# ProPrj___2026-05-07.net
KiCad netlist of a schematic drawn in EasyEDA Pro
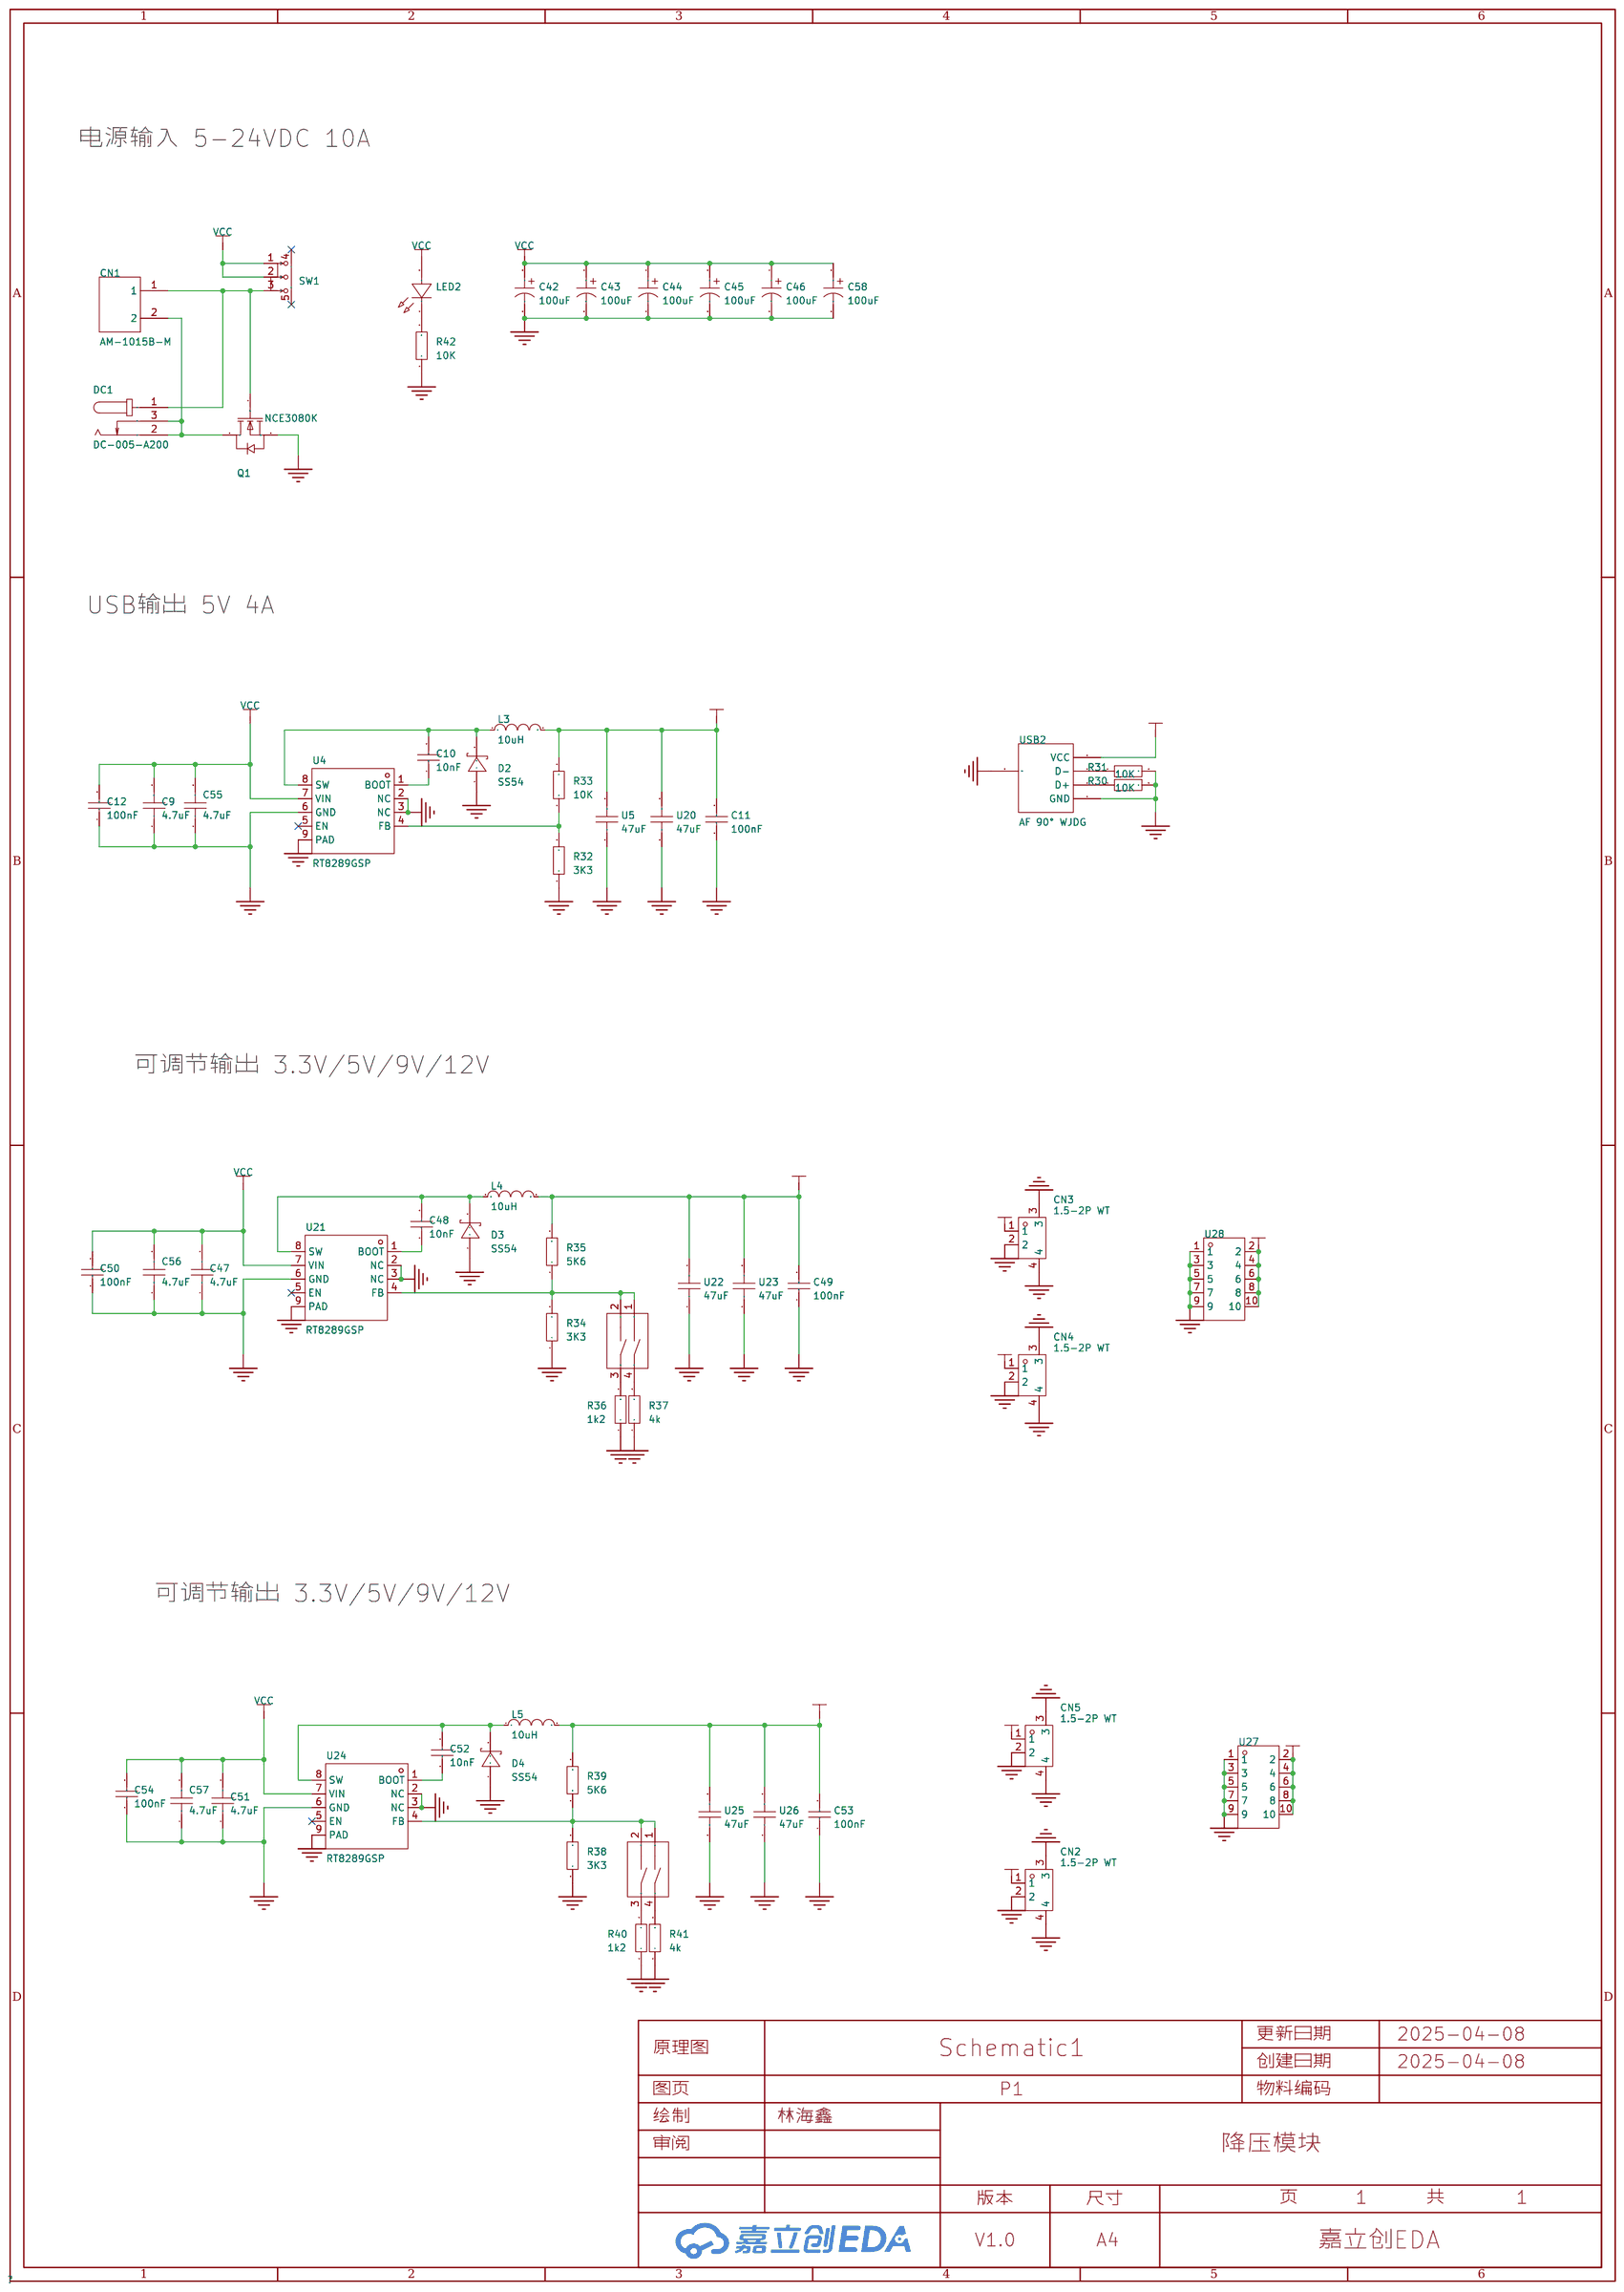
[diagram p0: schematic sheet]

(export (version "E")
  (design (tool "Eeschema 10.0.6"))
  (components
    (comp (ref "C9")
      (value "4.7uF")
      (fields
        (field (name "Manufacturer Part") "CL31B475KBHNNNE")
        (field (name "Manufacturer") "SAMSUNG(三星)")
      )
      (libsource (lib "easyedapro") (part "tcc0603x5r475k250ct"))
    )
    (comp (ref "C10")
      (value "10nF")
      (footprint "easyedapro:C0402")
      (description "容值:100nF;精度:±10%;额定电压:16V;材质(温度系数):X7R;")
      (fields
        (field (name "Manufacturer Part") "CC0603KRX7R9BB103")
        (field (name "Manufacturer") "YAGEO(国巨)")
      )
      (libsource (lib "easyedapro") (part "CL05B104KO5NNNC"))
    )
    (comp (ref "C11")
      (value "100nF")
      (footprint "easyedapro:C0402")
      (description "容值:100nF;精度:±10%;额定电压:16V;材质(温度系数):X7R;")
      (fields
        (field (name "Manufacturer Part") "CGA0603X7R104K500JT")
        (field (name "Manufacturer") "HRE(芯声)")
      )
      (libsource (lib "easyedapro") (part "CL05B104KO5NNNC"))
    )
    (comp (ref "C12")
      (value "100nF")
      (footprint "easyedapro:C0402")
      (description "容值:100nF;精度:±10%;额定电压:16V;材质(温度系数):X7R;")
      (fields
        (field (name "Manufacturer Part") "CGA0603X7R104K500JT")
        (field (name "Manufacturer") "HRE(芯声)")
      )
      (libsource (lib "easyedapro") (part "CL05B104KO5NNNC"))
    )
    (comp (ref "C42")
      (value "100uF")
      (footprint "easyedapro:CAP-SMD_BD6.3-L6.6-W6.6-LS7.6-FD-1")
      (description "容值:100uF;精度:±20%;额定电压:35V;纹波电流:230mA@120Hz;等效串联电阻:600mΩ@100kHz;")
      (fields
        (field (name "Manufacturer Part") "RVE100UF35V67RV0072")
        (field (name "Manufacturer") "KNSCHA(科尼盛)")
      )
      (libsource (lib "easyedapro") (part "rve100uf35v67rv0072"))
    )
    (comp (ref "C43")
      (value "100uF")
      (footprint "easyedapro:CAP-SMD_BD6.3-L6.6-W6.6-LS7.6-FD-1")
      (description "容值:100uF;精度:±20%;额定电压:35V;纹波电流:230mA@120Hz;等效串联电阻:600mΩ@100kHz;")
      (fields
        (field (name "Manufacturer Part") "RVE100UF35V67RV0072")
        (field (name "Manufacturer") "KNSCHA(科尼盛)")
      )
      (libsource (lib "easyedapro") (part "rve100uf35v67rv0072"))
    )
    (comp (ref "C44")
      (value "100uF")
      (footprint "easyedapro:CAP-SMD_BD6.3-L6.6-W6.6-LS7.6-FD-1")
      (description "容值:100uF;精度:±20%;额定电压:35V;纹波电流:230mA@120Hz;等效串联电阻:600mΩ@100kHz;")
      (fields
        (field (name "Manufacturer Part") "RVE100UF35V67RV0072")
        (field (name "Manufacturer") "KNSCHA(科尼盛)")
      )
      (libsource (lib "easyedapro") (part "rve100uf35v67rv0072"))
    )
    (comp (ref "C45")
      (value "100uF")
      (footprint "easyedapro:CAP-SMD_BD6.3-L6.6-W6.6-LS7.6-FD-1")
      (description "容值:100uF;精度:±20%;额定电压:35V;纹波电流:230mA@120Hz;等效串联电阻:600mΩ@100kHz;")
      (fields
        (field (name "Manufacturer Part") "RVE100UF35V67RV0072")
        (field (name "Manufacturer") "KNSCHA(科尼盛)")
      )
      (libsource (lib "easyedapro") (part "rve100uf35v67rv0072"))
    )
    (comp (ref "C46")
      (value "100uF")
      (footprint "easyedapro:CAP-SMD_BD6.3-L6.6-W6.6-LS7.6-FD-1")
      (description "容值:100uF;精度:±20%;额定电压:35V;纹波电流:230mA@120Hz;等效串联电阻:600mΩ@100kHz;")
      (fields
        (field (name "Manufacturer Part") "RVE100UF35V67RV0072")
        (field (name "Manufacturer") "KNSCHA(科尼盛)")
      )
      (libsource (lib "easyedapro") (part "rve100uf35v67rv0072"))
    )
    (comp (ref "C47")
      (value "4.7uF")
      (fields
        (field (name "Manufacturer Part") "CL31B475KBHNNNE")
        (field (name "Manufacturer") "SAMSUNG(三星)")
      )
      (libsource (lib "easyedapro") (part "tcc0603x5r475k250ct"))
    )
    (comp (ref "C48")
      (value "10nF")
      (footprint "easyedapro:C0402")
      (description "容值:100nF;精度:±10%;额定电压:16V;材质(温度系数):X7R;")
      (fields
        (field (name "Manufacturer Part") "CC0603KRX7R9BB103")
        (field (name "Manufacturer") "YAGEO(国巨)")
      )
      (libsource (lib "easyedapro") (part "CL05B104KO5NNNC"))
    )
    (comp (ref "C49")
      (value "100nF")
      (footprint "easyedapro:C0402")
      (description "容值:100nF;精度:±10%;额定电压:16V;材质(温度系数):X7R;")
      (fields
        (field (name "Manufacturer Part") "CGA0603X7R104K500JT")
        (field (name "Manufacturer") "HRE(芯声)")
      )
      (libsource (lib "easyedapro") (part "CL05B104KO5NNNC"))
    )
    (comp (ref "C50")
      (value "100nF")
      (footprint "easyedapro:C0402")
      (description "容值:100nF;精度:±10%;额定电压:16V;材质(温度系数):X7R;")
      (fields
        (field (name "Manufacturer Part") "CGA0603X7R104K500JT")
        (field (name "Manufacturer") "HRE(芯声)")
      )
      (libsource (lib "easyedapro") (part "CL05B104KO5NNNC"))
    )
    (comp (ref "C51")
      (value "4.7uF")
      (fields
        (field (name "Manufacturer Part") "CL31B475KBHNNNE")
        (field (name "Manufacturer") "SAMSUNG(三星)")
      )
      (libsource (lib "easyedapro") (part "tcc0603x5r475k250ct"))
    )
    (comp (ref "C52")
      (value "10nF")
      (footprint "easyedapro:C0402")
      (description "容值:100nF;精度:±10%;额定电压:16V;材质(温度系数):X7R;")
      (fields
        (field (name "Manufacturer Part") "CC0603KRX7R9BB103")
        (field (name "Manufacturer") "YAGEO(国巨)")
      )
      (libsource (lib "easyedapro") (part "CL05B104KO5NNNC"))
    )
    (comp (ref "C53")
      (value "100nF")
      (footprint "easyedapro:C0402")
      (description "容值:100nF;精度:±10%;额定电压:16V;材质(温度系数):X7R;")
      (fields
        (field (name "Manufacturer Part") "CGA0603X7R104K500JT")
        (field (name "Manufacturer") "HRE(芯声)")
      )
      (libsource (lib "easyedapro") (part "CL05B104KO5NNNC"))
    )
    (comp (ref "C54")
      (value "100nF")
      (footprint "easyedapro:C0402")
      (description "容值:100nF;精度:±10%;额定电压:16V;材质(温度系数):X7R;")
      (fields
        (field (name "Manufacturer Part") "CGA0603X7R104K500JT")
        (field (name "Manufacturer") "HRE(芯声)")
      )
      (libsource (lib "easyedapro") (part "CL05B104KO5NNNC"))
    )
    (comp (ref "C55")
      (value "4.7uF")
      (fields
        (field (name "Manufacturer Part") "CL31B475KBHNNNE")
        (field (name "Manufacturer") "SAMSUNG(三星)")
      )
      (libsource (lib "easyedapro") (part "tcc0603x5r475k250ct"))
    )
    (comp (ref "C56")
      (value "4.7uF")
      (fields
        (field (name "Manufacturer Part") "CL31B475KBHNNNE")
        (field (name "Manufacturer") "SAMSUNG(三星)")
      )
      (libsource (lib "easyedapro") (part "tcc0603x5r475k250ct"))
    )
    (comp (ref "C57")
      (value "4.7uF")
      (fields
        (field (name "Manufacturer Part") "CL31B475KBHNNNE")
        (field (name "Manufacturer") "SAMSUNG(三星)")
      )
      (libsource (lib "easyedapro") (part "tcc0603x5r475k250ct"))
    )
    (comp (ref "C58")
      (value "100uF")
      (footprint "easyedapro:CAP-SMD_BD6.3-L6.6-W6.6-LS7.6-FD-1")
      (description "容值:100uF;精度:±20%;额定电压:35V;纹波电流:230mA@120Hz;等效串联电阻:600mΩ@100kHz;")
      (fields
        (field (name "Manufacturer Part") "RVE100UF35V67RV0072")
        (field (name "Manufacturer") "KNSCHA(科尼盛)")
      )
      (libsource (lib "easyedapro") (part "rve100uf35v67rv0072"))
    )
    (comp (ref "CN1")
      (value "AM-1015B-M")
      (footprint "easyedapro:CONN-TH_AM-1015B-M")
      (description "类别:-;类型1:-;")
      (fields (field (name "Manufacturer") "AMASS(艾迈斯)"))
      (libsource (lib "easyedapro") (part "AM-1015B-M"))
    )
    (comp (ref "CN2")
      (value "1.5-2P WT")
      (footprint "easyedapro:CONN-SMD_1.5-2P-WT")
      (description "插针结构:1x2P;间距:1.5mm;安装方式:卧贴;参考系列:ZH;总PIN数:2P;排数:1;每排PIN数:2;行距:-;额定电流:1A;工作温度范围:-25°C~+85°C;")
      (fields (field (name "Manufacturer") "SHOU HAN(首韩)"))
      (libsource (lib "easyedapro") (part "1.5-2P WT"))
    )
    (comp (ref "CN3")
      (value "1.5-2P WT")
      (footprint "easyedapro:CONN-SMD_1.5-2P-WT")
      (description "插针结构:1x2P;间距:1.5mm;安装方式:卧贴;参考系列:ZH;总PIN数:2P;排数:1;每排PIN数:2;行距:-;额定电流:1A;工作温度范围:-25°C~+85°C;")
      (fields (field (name "Manufacturer") "SHOU HAN(首韩)"))
      (libsource (lib "easyedapro") (part "1.5-2P WT"))
    )
    (comp (ref "CN4")
      (value "1.5-2P WT")
      (footprint "easyedapro:CONN-SMD_1.5-2P-WT")
      (description "插针结构:1x2P;间距:1.5mm;安装方式:卧贴;参考系列:ZH;总PIN数:2P;排数:1;每排PIN数:2;行距:-;额定电流:1A;工作温度范围:-25°C~+85°C;")
      (fields (field (name "Manufacturer") "SHOU HAN(首韩)"))
      (libsource (lib "easyedapro") (part "1.5-2P WT"))
    )
    (comp (ref "CN5")
      (value "1.5-2P WT")
      (footprint "easyedapro:CONN-SMD_1.5-2P-WT")
      (description "插针结构:1x2P;间距:1.5mm;安装方式:卧贴;参考系列:ZH;总PIN数:2P;排数:1;每排PIN数:2;行距:-;额定电流:1A;工作温度范围:-25°C~+85°C;")
      (fields (field (name "Manufacturer") "SHOU HAN(首韩)"))
      (libsource (lib "easyedapro") (part "1.5-2P WT"))
    )
    (comp (ref "D2")
      (value "SS54")
      (footprint "easyedapro:SMA_L4.4-W2.8-LS5.4-R-RD")
      (description "正向压降(Vf):550mV@5A;直流反向耐压(Vr):40V;平均整流电流(Io):5A;")
      (fields (field (name "Manufacturer") "MDD"))
      (libsource (lib "easyedapro") (part "SS54_C22452"))
    )
    (comp (ref "D3")
      (value "SS54")
      (footprint "easyedapro:SMA_L4.4-W2.8-LS5.4-R-RD")
      (description "正向压降(Vf):550mV@5A;直流反向耐压(Vr):40V;平均整流电流(Io):5A;")
      (fields (field (name "Manufacturer") "MDD"))
      (libsource (lib "easyedapro") (part "SS54_C22452"))
    )
    (comp (ref "D4")
      (value "SS54")
      (footprint "easyedapro:SMA_L4.4-W2.8-LS5.4-R-RD")
      (description "正向压降(Vf):550mV@5A;直流反向耐压(Vr):40V;平均整流电流(Io):5A;")
      (fields (field (name "Manufacturer") "MDD"))
      (libsource (lib "easyedapro") (part "SS54_C22452"))
    )
    (comp (ref "DC1")
      (value "DC-005-A200")
      (footprint "easyedapro:DC-IN-TH_DC-005-A200")
      (description "连接器类型:DC电源插座;安装方式:弯插;触点内径:2mm;触点外径:6.4mm;额定电流:3A;额定电压:30V;工作温度范围:-20°C~+70°C;")
      (fields (field (name "Manufacturer") "XUNPU(讯普)"))
      (libsource (lib "easyedapro") (part "DC-005-A200"))
    )
    (comp (ref "L3")
      (value "10uH")
      (footprint "easyedapro:IND-SMD_L7.3-W6.8")
      (description "电感值:10uH;精度:±20%;额定电流:4.5A;饱和电流(Isat):5.5A;类型:一体成型电感;")
      (fields (field (name "Manufacturer Part") "FXL0630-100-M") (field (name "Manufacturer") "cjiang(长江微电)"))
      (libsource (lib "easyedapro") (part "FXL0630-100-M"))
    )
    (comp (ref "L4")
      (value "10uH")
      (footprint "easyedapro:IND-SMD_L7.3-W6.8")
      (description "电感值:10uH;精度:±20%;额定电流:4.5A;饱和电流(Isat):5.5A;类型:一体成型电感;")
      (fields (field (name "Manufacturer Part") "FXL0630-100-M") (field (name "Manufacturer") "cjiang(长江微电)"))
      (libsource (lib "easyedapro") (part "FXL0630-100-M"))
    )
    (comp (ref "L5")
      (value "10uH")
      (footprint "easyedapro:IND-SMD_L7.3-W6.8")
      (description "电感值:10uH;精度:±20%;额定电流:4.5A;饱和电流(Isat):5.5A;类型:一体成型电感;")
      (fields (field (name "Manufacturer Part") "FXL0630-100-M") (field (name "Manufacturer") "cjiang(长江微电)"))
      (libsource (lib "easyedapro") (part "FXL0630-100-M"))
    )
    (comp (ref "LED2")
      (value "XL-1608SURC-06")
      (footprint "easyedapro:LED0603-RD_RED")
      (description "发光颜色:红色;功率:55mW;正向电流:25mA;主波长:617nm~621nm;透镜颜色:无色透明透镜;色温:-;发光角度:120°;载带方式:正贴;工作温度:-30°C~+85°C;")
      (fields (field (name "Manufacturer") "XINGLIGHT(成兴光)"))
      (libsource (lib "easyedapro") (part "XL-1608SURC-06"))
    )
    (comp (ref "Q1")
      (value "NCE3080K")
      (footprint "easyedapro:TO-252-2_L6.6-W6.1-P4.57-LS9.9-TL-CW")
      (fields (field (name "Manufacturer") "NCE(无锡新洁能)"))
      (libsource (lib "easyedapro") (part "NCE3080K"))
    )
    (comp (ref "R30") (value "10K") (footprint "easyedapro:R0603") (libsource (lib "easyedapro") (part "电阻")))
    (comp (ref "R31") (value "10K") (footprint "easyedapro:R0603") (libsource (lib "easyedapro") (part "电阻")))
    (comp (ref "R32") (value "3K3") (footprint "easyedapro:R0603") (libsource (lib "easyedapro") (part "电阻")))
    (comp (ref "R33") (value "10K") (footprint "easyedapro:R0603") (libsource (lib "easyedapro") (part "电阻")))
    (comp (ref "R34") (value "3K3") (footprint "easyedapro:R0603") (libsource (lib "easyedapro") (part "电阻")))
    (comp (ref "R35") (value "5K6") (footprint "easyedapro:R0603") (libsource (lib "easyedapro") (part "电阻")))
    (comp (ref "R36") (value "1k2") (footprint "easyedapro:R0603") (libsource (lib "easyedapro") (part "电阻")))
    (comp (ref "R37") (value "4k") (footprint "easyedapro:R0603") (libsource (lib "easyedapro") (part "电阻")))
    (comp (ref "R38") (value "3K3") (footprint "easyedapro:R0603") (libsource (lib "easyedapro") (part "电阻")))
    (comp (ref "R39") (value "5K6") (footprint "easyedapro:R0603") (libsource (lib "easyedapro") (part "电阻")))
    (comp (ref "R40") (value "1k2") (footprint "easyedapro:R0603") (libsource (lib "easyedapro") (part "电阻")))
    (comp (ref "R41") (value "4k") (footprint "easyedapro:R0603") (libsource (lib "easyedapro") (part "电阻")))
    (comp (ref "R42") (value "10K") (footprint "easyedapro:R0603") (libsource (lib "easyedapro") (part "电阻")))
    (comp (ref "SW1")
      (value "SS-12D11L5")
      (footprint "easyedapro:SW-TH_SS-12D11L5")
      (description "电路结构:单刀双掷;安装方式:侧插;开关颜色:黑色;额定电流(DC):3A;额定电压(DC):125V;额定电流(AC):3A;额定电压(AC):125V;机械寿命:1万次;")
      (fields (field (name "Manufacturer") "XKB Connectivity(中国星坤)"))
      (libsource (lib "easyedapro") (part "SS-12D11L5"))
    )
    (comp (ref "SW2")
      (value "DSHP02TSGER")
      (footprint "easyedapro:SW-SMD_DSHP02TSGER")
      (description "电路结构:单刀单掷;开关位数:2位;额定电流:25mA;额定电压:24V;使用寿命:3千次;颜色:黑色;")
      (fields (field (name "Manufacturer") "康深"))
      (libsource (lib "easyedapro") (part "dshp02tsger"))
    )
    (comp (ref "SW3")
      (value "DSHP02TSGER")
      (footprint "easyedapro:SW-SMD_DSHP02TSGER")
      (description "电路结构:单刀单掷;开关位数:2位;额定电流:25mA;额定电压:24V;使用寿命:3千次;颜色:黑色;")
      (fields (field (name "Manufacturer") "康深"))
      (libsource (lib "easyedapro") (part "dshp02tsger"))
    )
    (comp (ref "U4")
      (value "RT8289GSP")
      (footprint "easyedapro:SOIC-8_L5.0-W4.0-P1.27-LS6.0-BL-EP2.0")
      (description "功能类型:降压型;输出类型:可调;输入电压:5.5V~32V;输出电压:1.222V~26V;输出电流(最大值):5A;")
      (fields (field (name "Manufacturer") "RICHTEK(立锜)"))
      (libsource (lib "easyedapro") (part "RT8289GSP"))
    )
    (comp (ref "U5")
      (value "47uF")
      (fields
        (field (name "Manufacturer Part") "CL31A476MPHNNNE")
        (field (name "Manufacturer") "SAMSUNG(三星)")
      )
      (libsource (lib "easyedapro") (part "cga0805x5r476m100mt"))
    )
    (comp (ref "U20")
      (value "47uF")
      (fields
        (field (name "Manufacturer Part") "CL31A476MPHNNNE")
        (field (name "Manufacturer") "SAMSUNG(三星)")
      )
      (libsource (lib "easyedapro") (part "cga0805x5r476m100mt"))
    )
    (comp (ref "U21")
      (value "RT8289GSP")
      (footprint "easyedapro:SOIC-8_L5.0-W4.0-P1.27-LS6.0-BL-EP2.0")
      (description "功能类型:降压型;输出类型:可调;输入电压:5.5V~32V;输出电压:1.222V~26V;输出电流(最大值):5A;")
      (fields (field (name "Manufacturer") "RICHTEK(立锜)"))
      (libsource (lib "easyedapro") (part "RT8289GSP"))
    )
    (comp (ref "U22")
      (value "47uF")
      (fields
        (field (name "Manufacturer Part") "CL31A476MPHNNNE")
        (field (name "Manufacturer") "SAMSUNG(三星)")
      )
      (libsource (lib "easyedapro") (part "cga0805x5r476m100mt"))
    )
    (comp (ref "U23")
      (value "47uF")
      (fields
        (field (name "Manufacturer Part") "CL31A476MPHNNNE")
        (field (name "Manufacturer") "SAMSUNG(三星)")
      )
      (libsource (lib "easyedapro") (part "cga0805x5r476m100mt"))
    )
    (comp (ref "U24")
      (value "RT8289GSP")
      (footprint "easyedapro:SOIC-8_L5.0-W4.0-P1.27-LS6.0-BL-EP2.0")
      (description "功能类型:降压型;输出类型:可调;输入电压:5.5V~32V;输出电压:1.222V~26V;输出电流(最大值):5A;")
      (fields (field (name "Manufacturer") "RICHTEK(立锜)"))
      (libsource (lib "easyedapro") (part "RT8289GSP"))
    )
    (comp (ref "U25")
      (value "47uF")
      (fields
        (field (name "Manufacturer Part") "CL31A476MPHNNNE")
        (field (name "Manufacturer") "SAMSUNG(三星)")
      )
      (libsource (lib "easyedapro") (part "cga0805x5r476m100mt"))
    )
    (comp (ref "U26")
      (value "47uF")
      (fields
        (field (name "Manufacturer Part") "CL31A476MPHNNNE")
        (field (name "Manufacturer") "SAMSUNG(三星)")
      )
      (libsource (lib "easyedapro") (part "cga0805x5r476m100mt"))
    )
    (comp (ref "U27")
      (value "ZX-PZ2.54-2-5PZZ")
      (footprint "easyedapro:HDR-TH_10P-P2.54-V-M-R2-C5-S2.54")
      (fields (field (name "Manufacturer") "Megastar(兆星)"))
      (libsource (lib "easyedapro") (part "ZX-PZ2.54-2-5PZZ"))
    )
    (comp (ref "U28")
      (value "ZX-PZ2.54-2-5PZZ")
      (footprint "easyedapro:HDR-TH_10P-P2.54-V-M-R2-C5-S2.54")
      (fields (field (name "Manufacturer") "Megastar(兆星)"))
      (libsource (lib "easyedapro") (part "ZX-PZ2.54-2-5PZZ"))
    )
    (comp (ref "USB2")
      (value "AF 90° WJDG")
      (footprint "easyedapro:USB-A-TH_AF-WJDG")
      (description "连接器类型:Type-A;标准:USB 2.0;公母:母;端口数量:1;触点数量:4P;安装方式:弯插;额定电流 - 电源:1.5A;工作温度范围:-25°C~+85°C;")
      (fields (field (name "Manufacturer") "SHOU HAN(首韩)"))
      (libsource (lib "easyedapro") (part "AF 90° WJDG"))
    )
  )
  (nets
    (net (code "1") (name "5V_USB") (class "Default")
      (node (ref "C11") (pin "2") (pinfunction "2_2") (pintype "input"))
      (node (ref "L3") (pin "2") (pinfunction "2_2") (pintype "unspecified"))
      (node (ref "R33") (pin "2") (pinfunction "2_2") (pintype "input"))
      (node (ref "U20") (pin "2") (pinfunction "2_2") (pintype "unspecified"))
      (node (ref "U5") (pin "2") (pinfunction "2_2") (pintype "unspecified"))
      (node (ref "USB2") (pin "1") (pinfunction "VCC_1") (pintype "input"))
    )
    (net (code "2") (name "GND") (class "Default")
      (node (ref "C11") (pin "1") (pinfunction "1_1") (pintype "input"))
      (node (ref "C12") (pin "1") (pinfunction "1_1") (pintype "input"))
      (node (ref "C42") (pin "2") (pinfunction "2_2") (pintype "input"))
      (node (ref "C43") (pin "2") (pinfunction "2_2") (pintype "input"))
      (node (ref "C44") (pin "2") (pinfunction "2_2") (pintype "input"))
      (node (ref "C45") (pin "2") (pinfunction "2_2") (pintype "input"))
      (node (ref "C46") (pin "2") (pinfunction "2_2") (pintype "input"))
      (node (ref "C47") (pin "1") (pinfunction "1_1") (pintype "unspecified"))
      (node (ref "C49") (pin "1") (pinfunction "1_1") (pintype "input"))
      (node (ref "C50") (pin "1") (pinfunction "1_1") (pintype "input"))
      (node (ref "C51") (pin "1") (pinfunction "1_1") (pintype "unspecified"))
      (node (ref "C53") (pin "1") (pinfunction "1_1") (pintype "input"))
      (node (ref "C54") (pin "1") (pinfunction "1_1") (pintype "input"))
      (node (ref "C55") (pin "1") (pinfunction "1_1") (pintype "unspecified"))
      (node (ref "C56") (pin "1") (pinfunction "1_1") (pintype "unspecified"))
      (node (ref "C57") (pin "1") (pinfunction "1_1") (pintype "unspecified"))
      (node (ref "C58") (pin "2") (pinfunction "2_2") (pintype "input"))
      (node (ref "C9") (pin "1") (pinfunction "1_1") (pintype "unspecified"))
      (node (ref "CN2") (pin "2") (pinfunction "2_2") (pintype "unspecified"))
      (node (ref "CN2") (pin "3") (pinfunction "3_3") (pintype "unspecified"))
      (node (ref "CN2") (pin "4") (pinfunction "4_4") (pintype "unspecified"))
      (node (ref "CN3") (pin "2") (pinfunction "2_2") (pintype "unspecified"))
      (node (ref "CN3") (pin "3") (pinfunction "3_3") (pintype "unspecified"))
      (node (ref "CN3") (pin "4") (pinfunction "4_4") (pintype "unspecified"))
      (node (ref "CN4") (pin "2") (pinfunction "2_2") (pintype "unspecified"))
      (node (ref "CN4") (pin "3") (pinfunction "3_3") (pintype "unspecified"))
      (node (ref "CN4") (pin "4") (pinfunction "4_4") (pintype "unspecified"))
      (node (ref "CN5") (pin "2") (pinfunction "2_2") (pintype "unspecified"))
      (node (ref "CN5") (pin "3") (pinfunction "3_3") (pintype "unspecified"))
      (node (ref "CN5") (pin "4") (pinfunction "4_4") (pintype "unspecified"))
      (node (ref "D2") (pin "1") (pinfunction "A_1") (pintype "unspecified"))
      (node (ref "D3") (pin "1") (pinfunction "A_1") (pintype "unspecified"))
      (node (ref "D4") (pin "1") (pinfunction "A_1") (pintype "unspecified"))
      (node (ref "Q1") (pin "3") (pinfunction "S_3") (pintype "unspecified"))
      (node (ref "R30") (pin "2") (pinfunction "2_2") (pintype "input"))
      (node (ref "R31") (pin "2") (pinfunction "2_2") (pintype "input"))
      (node (ref "R32") (pin "1") (pinfunction "1_1") (pintype "input"))
      (node (ref "R34") (pin "1") (pinfunction "1_1") (pintype "input"))
      (node (ref "R36") (pin "1") (pinfunction "1_1") (pintype "input"))
      (node (ref "R37") (pin "1") (pinfunction "1_1") (pintype "input"))
      (node (ref "R38") (pin "1") (pinfunction "1_1") (pintype "input"))
      (node (ref "R40") (pin "1") (pinfunction "1_1") (pintype "input"))
      (node (ref "R41") (pin "1") (pinfunction "1_1") (pintype "input"))
      (node (ref "R42") (pin "1") (pinfunction "1_1") (pintype "input"))
      (node (ref "U20") (pin "1") (pinfunction "1_1") (pintype "unspecified"))
      (node (ref "U21") (pin "2") (pinfunction "NC_2") (pintype "unspecified"))
      (node (ref "U21") (pin "3") (pinfunction "NC_3") (pintype "unspecified"))
      (node (ref "U21") (pin "6") (pinfunction "GND_6") (pintype "unspecified"))
      (node (ref "U21") (pin "9") (pinfunction "PAD_9") (pintype "unspecified"))
      (node (ref "U22") (pin "1") (pinfunction "1_1") (pintype "unspecified"))
      (node (ref "U23") (pin "1") (pinfunction "1_1") (pintype "unspecified"))
      (node (ref "U24") (pin "2") (pinfunction "NC_2") (pintype "unspecified"))
      (node (ref "U24") (pin "3") (pinfunction "NC_3") (pintype "unspecified"))
      (node (ref "U24") (pin "6") (pinfunction "GND_6") (pintype "unspecified"))
      (node (ref "U24") (pin "9") (pinfunction "PAD_9") (pintype "unspecified"))
      (node (ref "U25") (pin "1") (pinfunction "1_1") (pintype "unspecified"))
      (node (ref "U26") (pin "1") (pinfunction "1_1") (pintype "unspecified"))
      (node (ref "U27") (pin "1") (pinfunction "1_1") (pintype "unspecified"))
      (node (ref "U27") (pin "3") (pinfunction "3_3") (pintype "unspecified"))
      (node (ref "U27") (pin "5") (pinfunction "5_5") (pintype "unspecified"))
      (node (ref "U27") (pin "7") (pinfunction "7_7") (pintype "unspecified"))
      (node (ref "U27") (pin "9") (pinfunction "9_9") (pintype "unspecified"))
      (node (ref "U28") (pin "1") (pinfunction "1_1") (pintype "unspecified"))
      (node (ref "U28") (pin "3") (pinfunction "3_3") (pintype "unspecified"))
      (node (ref "U28") (pin "5") (pinfunction "5_5") (pintype "unspecified"))
      (node (ref "U28") (pin "7") (pinfunction "7_7") (pintype "unspecified"))
      (node (ref "U28") (pin "9") (pinfunction "9_9") (pintype "unspecified"))
      (node (ref "U4") (pin "2") (pinfunction "NC_2") (pintype "unspecified"))
      (node (ref "U4") (pin "3") (pinfunction "NC_3") (pintype "unspecified"))
      (node (ref "U4") (pin "6") (pinfunction "GND_6") (pintype "unspecified"))
      (node (ref "U4") (pin "9") (pinfunction "PAD_9") (pintype "unspecified"))
      (node (ref "U5") (pin "1") (pinfunction "1_1") (pintype "unspecified"))
      (node (ref "USB2") (pin "4") (pinfunction "GND_4") (pintype "input"))
      (node (ref "USB2") (pin "5") (pinfunction "SHLD_5") (pintype "unspecified"))
    )
    (net (code "3") (name "Net-(D2-K)") (class "Default")
      (node (ref "C10") (pin "2") (pinfunction "2_2") (pintype "input"))
      (node (ref "D2") (pin "2") (pinfunction "K_2") (pintype "unspecified"))
      (node (ref "L3") (pin "1") (pinfunction "1_1") (pintype "unspecified"))
      (node (ref "U4") (pin "8") (pinfunction "SW_8") (pintype "unspecified"))
    )
    (net (code "4") (name "Net-(D3-K)") (class "Default")
      (node (ref "C48") (pin "2") (pinfunction "2_2") (pintype "input"))
      (node (ref "D3") (pin "2") (pinfunction "K_2") (pintype "unspecified"))
      (node (ref "L4") (pin "1") (pinfunction "1_1") (pintype "unspecified"))
      (node (ref "U21") (pin "8") (pinfunction "SW_8") (pintype "unspecified"))
    )
    (net (code "5") (name "Net-(D4-K)") (class "Default")
      (node (ref "C52") (pin "2") (pinfunction "2_2") (pintype "input"))
      (node (ref "D4") (pin "2") (pinfunction "K_2") (pintype "unspecified"))
      (node (ref "L5") (pin "1") (pinfunction "1_1") (pintype "unspecified"))
      (node (ref "U24") (pin "8") (pinfunction "SW_8") (pintype "unspecified"))
    )
    (net (code "6") (name "Net-(LED2-K)") (class "Default")
      (node (ref "LED2") (pin "1") (pinfunction "K_1") (pintype "unspecified"))
      (node (ref "R42") (pin "2") (pinfunction "2_2") (pintype "input"))
    )
    (net (code "7") (name "Net-(Q1-D)") (class "Default")
      (node (ref "CN1") (pin "2") (pinfunction "2_2") (pintype "unspecified"))
      (node (ref "DC1") (pin "2") (pinfunction "2_2") (pintype "unspecified"))
      (node (ref "DC1") (pin "3") (pinfunction "3_3") (pintype "unspecified"))
      (node (ref "Q1") (pin "2") (pinfunction "D_2") (pintype "unspecified"))
    )
    (net (code "8") (name "Net-(Q1-G)") (class "Default")
      (node (ref "CN1") (pin "1") (pinfunction "1_1") (pintype "unspecified"))
      (node (ref "DC1") (pin "1") (pinfunction "1_1") (pintype "unspecified"))
      (node (ref "Q1") (pin "1") (pinfunction "G_1") (pintype "unspecified"))
      (node (ref "SW1") (pin "3") (pinfunction "3_3") (pintype "unspecified"))
    )
    (net (code "9") (name "Net-(R36-Pad2)") (class "Default")
      (node (ref "R36") (pin "2") (pinfunction "2_2") (pintype "input"))
      (node (ref "SW2") (pin "3") (pinfunction "3_3") (pintype "unspecified"))
    )
    (net (code "10") (name "Net-(R37-Pad2)") (class "Default")
      (node (ref "R37") (pin "2") (pinfunction "2_2") (pintype "input"))
      (node (ref "SW2") (pin "4") (pinfunction "4_4") (pintype "unspecified"))
    )
    (net (code "11") (name "Net-(R40-Pad2)") (class "Default")
      (node (ref "R40") (pin "2") (pinfunction "2_2") (pintype "input"))
      (node (ref "SW3") (pin "3") (pinfunction "3_3") (pintype "unspecified"))
    )
    (net (code "12") (name "Net-(R41-Pad2)") (class "Default")
      (node (ref "R41") (pin "2") (pinfunction "2_2") (pintype "input"))
      (node (ref "SW3") (pin "4") (pinfunction "4_4") (pintype "unspecified"))
    )
    (net (code "13") (name "Net-(U4-BOOT)") (class "Default")
      (node (ref "C10") (pin "1") (pinfunction "1_1") (pintype "input"))
      (node (ref "U4") (pin "1") (pinfunction "BOOT_1") (pintype "unspecified"))
    )
    (net (code "14") (name "Net-(U4-FB)") (class "Default")
      (node (ref "R32") (pin "2") (pinfunction "2_2") (pintype "input"))
      (node (ref "R33") (pin "1") (pinfunction "1_1") (pintype "input"))
      (node (ref "U4") (pin "4") (pinfunction "FB_4") (pintype "unspecified"))
    )
    (net (code "15") (name "Net-(U21-BOOT)") (class "Default")
      (node (ref "C48") (pin "1") (pinfunction "1_1") (pintype "input"))
      (node (ref "U21") (pin "1") (pinfunction "BOOT_1") (pintype "unspecified"))
    )
    (net (code "16") (name "Net-(U21-FB)") (class "Default")
      (node (ref "R34") (pin "2") (pinfunction "2_2") (pintype "input"))
      (node (ref "R35") (pin "1") (pinfunction "1_1") (pintype "input"))
      (node (ref "SW2") (pin "1") (pinfunction "1_1") (pintype "unspecified"))
      (node (ref "SW2") (pin "2") (pinfunction "2_2") (pintype "unspecified"))
      (node (ref "U21") (pin "4") (pinfunction "FB_4") (pintype "unspecified"))
    )
    (net (code "17") (name "Net-(U24-BOOT)") (class "Default")
      (node (ref "C52") (pin "1") (pinfunction "1_1") (pintype "input"))
      (node (ref "U24") (pin "1") (pinfunction "BOOT_1") (pintype "unspecified"))
    )
    (net (code "18") (name "Net-(U24-FB)") (class "Default")
      (node (ref "R38") (pin "2") (pinfunction "2_2") (pintype "input"))
      (node (ref "R39") (pin "1") (pinfunction "1_1") (pintype "input"))
      (node (ref "SW3") (pin "1") (pinfunction "1_1") (pintype "unspecified"))
      (node (ref "SW3") (pin "2") (pinfunction "2_2") (pintype "unspecified"))
      (node (ref "U24") (pin "4") (pinfunction "FB_4") (pintype "unspecified"))
    )
    (net (code "19") (name "Net-(USB2-D+)") (class "Default")
      (node (ref "R31") (pin "1") (pinfunction "1_1") (pintype "input"))
      (node (ref "USB2") (pin "3") (pinfunction "D+_3") (pintype "input"))
    )
    (net (code "20") (name "Net-(USB2-D-)") (class "Default")
      (node (ref "R30") (pin "1") (pinfunction "1_1") (pintype "input"))
      (node (ref "USB2") (pin "2") (pinfunction "D-_2") (pintype "input"))
    )
    (net (code "21") (name "VCC") (class "Default")
      (node (ref "C12") (pin "2") (pinfunction "2_2") (pintype "input"))
      (node (ref "C42") (pin "1") (pinfunction "1_1") (pintype "input"))
      (node (ref "C43") (pin "1") (pinfunction "1_1") (pintype "input"))
      (node (ref "C44") (pin "1") (pinfunction "1_1") (pintype "input"))
      (node (ref "C45") (pin "1") (pinfunction "1_1") (pintype "input"))
      (node (ref "C46") (pin "1") (pinfunction "1_1") (pintype "input"))
      (node (ref "C47") (pin "2") (pinfunction "2_2") (pintype "unspecified"))
      (node (ref "C50") (pin "2") (pinfunction "2_2") (pintype "input"))
      (node (ref "C51") (pin "2") (pinfunction "2_2") (pintype "unspecified"))
      (node (ref "C54") (pin "2") (pinfunction "2_2") (pintype "input"))
      (node (ref "C55") (pin "2") (pinfunction "2_2") (pintype "unspecified"))
      (node (ref "C56") (pin "2") (pinfunction "2_2") (pintype "unspecified"))
      (node (ref "C57") (pin "2") (pinfunction "2_2") (pintype "unspecified"))
      (node (ref "C58") (pin "1") (pinfunction "1_1") (pintype "input"))
      (node (ref "C9") (pin "2") (pinfunction "2_2") (pintype "unspecified"))
      (node (ref "LED2") (pin "2") (pinfunction "A_2") (pintype "unspecified"))
      (node (ref "SW1") (pin "1") (pinfunction "1_1") (pintype "unspecified"))
      (node (ref "SW1") (pin "2") (pinfunction "2_2") (pintype "unspecified"))
      (node (ref "U21") (pin "7") (pinfunction "VIN_7") (pintype "unspecified"))
      (node (ref "U24") (pin "7") (pinfunction "VIN_7") (pintype "unspecified"))
      (node (ref "U4") (pin "7") (pinfunction "VIN_7") (pintype "unspecified"))
    )
    (net (code "22") (name "VOUT1") (class "Default")
      (node (ref "C49") (pin "2") (pinfunction "2_2") (pintype "input"))
      (node (ref "CN3") (pin "1") (pinfunction "1_1") (pintype "unspecified"))
      (node (ref "CN4") (pin "1") (pinfunction "1_1") (pintype "unspecified"))
      (node (ref "L4") (pin "2") (pinfunction "2_2") (pintype "unspecified"))
      (node (ref "R35") (pin "2") (pinfunction "2_2") (pintype "input"))
      (node (ref "U22") (pin "2") (pinfunction "2_2") (pintype "unspecified"))
      (node (ref "U23") (pin "2") (pinfunction "2_2") (pintype "unspecified"))
      (node (ref "U28") (pin "10") (pinfunction "10_10") (pintype "unspecified"))
      (node (ref "U28") (pin "2") (pinfunction "2_2") (pintype "unspecified"))
      (node (ref "U28") (pin "4") (pinfunction "4_4") (pintype "unspecified"))
      (node (ref "U28") (pin "6") (pinfunction "6_6") (pintype "unspecified"))
      (node (ref "U28") (pin "8") (pinfunction "8_8") (pintype "unspecified"))
    )
    (net (code "23") (name "VOUT2") (class "Default")
      (node (ref "C53") (pin "2") (pinfunction "2_2") (pintype "input"))
      (node (ref "CN2") (pin "1") (pinfunction "1_1") (pintype "unspecified"))
      (node (ref "CN5") (pin "1") (pinfunction "1_1") (pintype "unspecified"))
      (node (ref "L5") (pin "2") (pinfunction "2_2") (pintype "unspecified"))
      (node (ref "R39") (pin "2") (pinfunction "2_2") (pintype "input"))
      (node (ref "U25") (pin "2") (pinfunction "2_2") (pintype "unspecified"))
      (node (ref "U26") (pin "2") (pinfunction "2_2") (pintype "unspecified"))
      (node (ref "U27") (pin "10") (pinfunction "10_10") (pintype "unspecified"))
      (node (ref "U27") (pin "2") (pinfunction "2_2") (pintype "unspecified"))
      (node (ref "U27") (pin "4") (pinfunction "4_4") (pintype "unspecified"))
      (node (ref "U27") (pin "6") (pinfunction "6_6") (pintype "unspecified"))
      (node (ref "U27") (pin "8") (pinfunction "8_8") (pintype "unspecified"))
    )
    (net (code "24") (name "unconnected-(SW1-Pad4)") (class "Default")
      (node (ref "SW1") (pin "4") (pinfunction "4_4") (pintype "unspecified+no_connect"))
    )
    (net (code "25") (name "unconnected-(SW1-Pad5)") (class "Default")
      (node (ref "SW1") (pin "5") (pinfunction "5_5") (pintype "unspecified+no_connect"))
    )
    (net (code "26") (name "unconnected-(U4-EN-Pad5)") (class "Default")
      (node (ref "U4") (pin "5") (pinfunction "EN_5") (pintype "unspecified+no_connect"))
    )
    (net (code "27") (name "unconnected-(U21-EN-Pad5)") (class "Default")
      (node (ref "U21") (pin "5") (pinfunction "EN_5") (pintype "unspecified+no_connect"))
    )
    (net (code "28") (name "unconnected-(U24-EN-Pad5)") (class "Default")
      (node (ref "U24") (pin "5") (pinfunction "EN_5") (pintype "unspecified+no_connect"))
    )
  )
)
